# ASK_Module_Receiver_RR3-XXX.net
KiCad netlist of a schematic drawn in Altium Designer
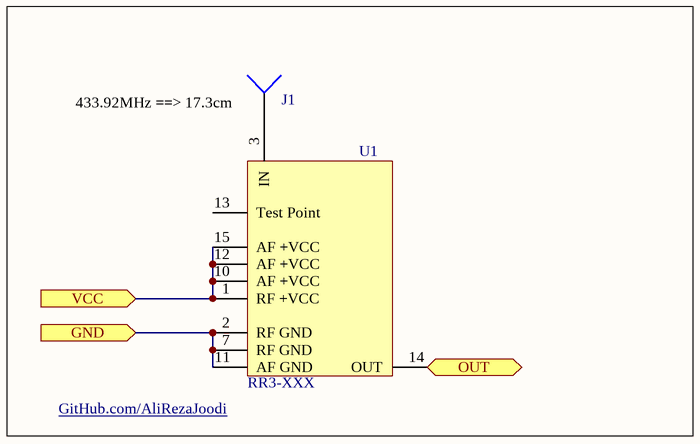
[diagram p0: ASK Module_Receiver_RR3-XXX.SchDoc]

(export (version "E")
  (design (tool "Eeschema 10.0.6"))
  (components
    (comp (ref "J1")
      (value "COAX-F")
      (footprint "PIN1")
      (description "Coax-F Connector")
      (fields (field (name "MANUFACTURER") "Generic Components") (field (name "PUBLISHER") "Altium Limited"))
      (libsource (lib "Miscellaneous Connectors") (part "COAX-F"))
    )
    (comp (ref "U1")
      (value "RR3-XXX")
      (footprint "RR3-XXX")
      (description "ASK RF Model")
      (libsource (lib "my Libraries") (part "RR3-XXX"))
    )
  )
  (nets
    (net (code "1") (name "/GND") (class "Default")
      (node (ref "U1") (pin "11") (pinfunction "AF_GND_11") (pintype "passive"))
      (node (ref "U1") (pin "2") (pinfunction "RF_GND_2") (pintype "passive"))
      (node (ref "U1") (pin "7") (pinfunction "RF_GND_7") (pintype "passive"))
    )
    (net (code "2") (name "/OUT") (class "Default")
      (node (ref "U1") (pin "14") (pinfunction "OUT_14") (pintype "passive"))
    )
    (net (code "3") (name "/VCC") (class "Default")
      (node (ref "U1") (pin "1") (pinfunction "RF_+VCC_1") (pintype "passive"))
      (node (ref "U1") (pin "10") (pinfunction "AF_+VCC_10") (pintype "passive"))
      (node (ref "U1") (pin "12") (pinfunction "AF_+VCC_12") (pintype "passive"))
      (node (ref "U1") (pin "15") (pinfunction "AF_+VCC_15") (pintype "passive"))
    )
    (net (code "4") (name "Net-(J1-A)") (class "Default")
      (node (ref "J1") (pin "1") (pinfunction "A_1") (pintype "passive"))
      (node (ref "U1") (pin "3") (pinfunction "IN_3") (pintype "passive"))
    )
    (net (code "5") (name "unconnected-(U1-Test_Point-Pad13)") (class "Default")
      (node (ref "U1") (pin "13") (pinfunction "Test_Point_13") (pintype "passive"))
    )
  )
)
